# stepperboard1.net
KiCad netlist of a schematic drawn in EAGLE
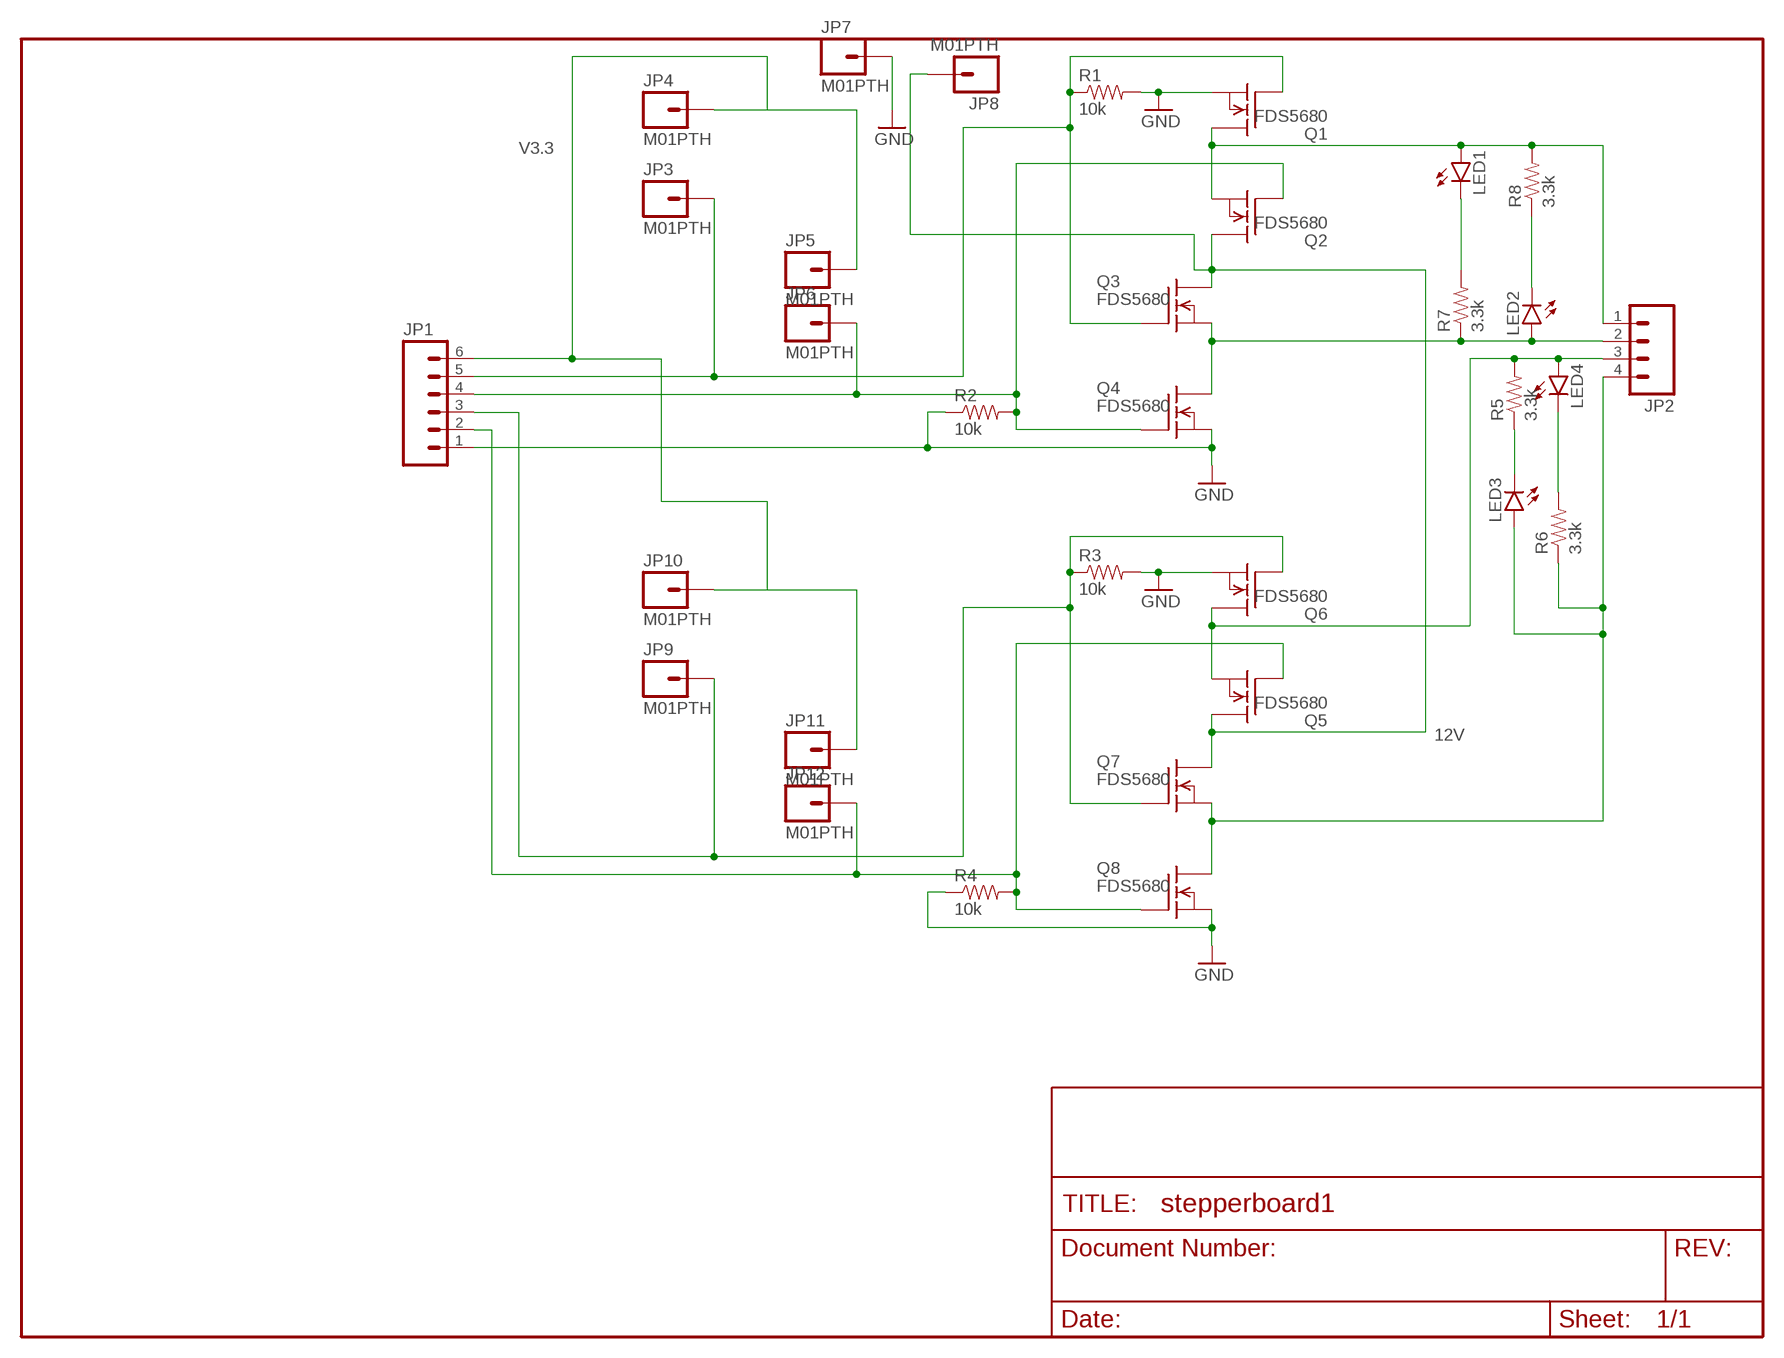
[diagram p0: schematic, sheet 1]

(export (version "E")
  (design (tool "Eeschema 10.0.6"))
  (components
    (comp (ref "JP1")
      (value "M06NO_SILK")
      (footprint "eagle-import:1X06_NO_SILK")
      (libsource (lib "eagle-import") (part "M06NO_SILK"))
    )
    (comp (ref "JP2")
      (value "M04LONGPADS")
      (footprint "eagle-import:1X04_LONGPADS")
      (libsource (lib "eagle-import") (part "M04LONGPADS"))
    )
    (comp (ref "JP3")
      (value "M01PTH")
      (footprint "eagle-import:1X01")
      (libsource (lib "eagle-import") (part "M01PTH"))
    )
    (comp (ref "JP4")
      (value "M01PTH")
      (footprint "eagle-import:1X01")
      (libsource (lib "eagle-import") (part "M01PTH"))
    )
    (comp (ref "JP5")
      (value "M01PTH")
      (footprint "eagle-import:1X01")
      (libsource (lib "eagle-import") (part "M01PTH"))
    )
    (comp (ref "JP6")
      (value "M01PTH")
      (footprint "eagle-import:1X01")
      (libsource (lib "eagle-import") (part "M01PTH"))
    )
    (comp (ref "JP7")
      (value "M01PTH")
      (footprint "eagle-import:1X01")
      (libsource (lib "eagle-import") (part "M01PTH"))
    )
    (comp (ref "JP8")
      (value "M01PTH")
      (footprint "eagle-import:1X01")
      (libsource (lib "eagle-import") (part "M01PTH"))
    )
    (comp (ref "JP9")
      (value "M01PTH")
      (footprint "eagle-import:1X01")
      (libsource (lib "eagle-import") (part "M01PTH"))
    )
    (comp (ref "JP10")
      (value "M01PTH")
      (footprint "eagle-import:1X01")
      (libsource (lib "eagle-import") (part "M01PTH"))
    )
    (comp (ref "JP11")
      (value "M01PTH")
      (footprint "eagle-import:1X01")
      (libsource (lib "eagle-import") (part "M01PTH"))
    )
    (comp (ref "JP12")
      (value "M01PTH")
      (footprint "eagle-import:1X01")
      (libsource (lib "eagle-import") (part "M01PTH"))
    )
    (comp (ref "LED1")
      (value "LED3MM")
      (footprint "eagle-import:LED3MM")
      (libsource (lib "eagle-import") (part "LED3MM"))
    )
    (comp (ref "LED2")
      (value "LED3MM")
      (footprint "eagle-import:LED3MM")
      (libsource (lib "eagle-import") (part "LED3MM"))
    )
    (comp (ref "LED3")
      (value "LED3MM")
      (footprint "eagle-import:LED3MM")
      (libsource (lib "eagle-import") (part "LED3MM"))
    )
    (comp (ref "LED4")
      (value "LED3MM")
      (footprint "eagle-import:LED3MM")
      (libsource (lib "eagle-import") (part "LED3MM"))
    )
    (comp (ref "Q1")
      (value "FDS5680")
      (footprint "eagle-import:SO-8")
      (libsource (lib "eagle-import") (part "FDS5680"))
    )
    (comp (ref "Q2")
      (value "FDS5680")
      (footprint "eagle-import:SO-8")
      (libsource (lib "eagle-import") (part "FDS5680"))
    )
    (comp (ref "Q3")
      (value "FDS5680")
      (footprint "eagle-import:SO-8")
      (libsource (lib "eagle-import") (part "FDS5680"))
    )
    (comp (ref "Q4")
      (value "FDS5680")
      (footprint "eagle-import:SO-8")
      (libsource (lib "eagle-import") (part "FDS5680"))
    )
    (comp (ref "Q5")
      (value "FDS5680")
      (footprint "eagle-import:SO-8")
      (libsource (lib "eagle-import") (part "FDS5680"))
    )
    (comp (ref "Q6")
      (value "FDS5680")
      (footprint "eagle-import:SO-8")
      (libsource (lib "eagle-import") (part "FDS5680"))
    )
    (comp (ref "Q7")
      (value "FDS5680")
      (footprint "eagle-import:SO-8")
      (libsource (lib "eagle-import") (part "FDS5680"))
    )
    (comp (ref "Q8")
      (value "FDS5680")
      (footprint "eagle-import:SO-8")
      (libsource (lib "eagle-import") (part "FDS5680"))
    )
    (comp (ref "R1")
      (value "10k")
      (footprint "eagle-import:0603-RES")
      (libsource (lib "eagle-import") (part "RESISTOR0603-RES"))
    )
    (comp (ref "R2")
      (value "10k")
      (footprint "eagle-import:0603-RES")
      (libsource (lib "eagle-import") (part "RESISTOR0603-RES"))
    )
    (comp (ref "R3")
      (value "10k")
      (footprint "eagle-import:0603-RES")
      (libsource (lib "eagle-import") (part "RESISTOR0603-RES"))
    )
    (comp (ref "R4")
      (value "10k")
      (footprint "eagle-import:0603-RES")
      (libsource (lib "eagle-import") (part "RESISTOR0603-RES"))
    )
    (comp (ref "R5")
      (value "3.3k")
      (footprint "eagle-import:0603-RES")
      (libsource (lib "eagle-import") (part "RESISTOR0603-RES"))
    )
    (comp (ref "R6")
      (value "3.3k")
      (footprint "eagle-import:0603-RES")
      (libsource (lib "eagle-import") (part "RESISTOR0603-RES"))
    )
    (comp (ref "R7")
      (value "3.3k")
      (footprint "eagle-import:0603-RES")
      (libsource (lib "eagle-import") (part "RESISTOR0603-RES"))
    )
    (comp (ref "R8")
      (value "3.3k")
      (footprint "eagle-import:0603-RES")
      (libsource (lib "eagle-import") (part "RESISTOR0603-RES"))
    )
  )
  (nets
    (net (code "1") (name "/12V") (class "Default")
      (node (ref "JP8") (pin "1") (pinfunction "1_1") (pintype "passive"))
      (node (ref "Q2") (pin "5") (pinfunction "D_5") (pintype "passive"))
      (node (ref "Q2") (pin "6") (pinfunction "D_6") (pintype "passive"))
      (node (ref "Q2") (pin "7") (pinfunction "D_7") (pintype "passive"))
      (node (ref "Q2") (pin "8") (pinfunction "D_8") (pintype "passive"))
      (node (ref "Q3") (pin "5") (pinfunction "D_5") (pintype "passive"))
      (node (ref "Q3") (pin "6") (pinfunction "D_6") (pintype "passive"))
      (node (ref "Q3") (pin "7") (pinfunction "D_7") (pintype "passive"))
      (node (ref "Q3") (pin "8") (pinfunction "D_8") (pintype "passive"))
      (node (ref "Q5") (pin "5") (pinfunction "D_5") (pintype "passive"))
      (node (ref "Q5") (pin "6") (pinfunction "D_6") (pintype "passive"))
      (node (ref "Q5") (pin "7") (pinfunction "D_7") (pintype "passive"))
      (node (ref "Q5") (pin "8") (pinfunction "D_8") (pintype "passive"))
      (node (ref "Q7") (pin "5") (pinfunction "D_5") (pintype "passive"))
      (node (ref "Q7") (pin "6") (pinfunction "D_6") (pintype "passive"))
      (node (ref "Q7") (pin "7") (pinfunction "D_7") (pintype "passive"))
      (node (ref "Q7") (pin "8") (pinfunction "D_8") (pintype "passive"))
    )
    (net (code "2") (name "/V3.3") (class "Default")
      (node (ref "JP1") (pin "6") (pinfunction "6_6") (pintype "passive"))
      (node (ref "JP10") (pin "1") (pinfunction "1_1") (pintype "passive"))
      (node (ref "JP11") (pin "1") (pinfunction "1_1") (pintype "passive"))
      (node (ref "JP4") (pin "1") (pinfunction "1_1") (pintype "passive"))
      (node (ref "JP5") (pin "1") (pinfunction "1_1") (pintype "passive"))
    )
    (net (code "3") (name "GND") (class "Default")
      (node (ref "JP1") (pin "1") (pinfunction "1_1") (pintype "passive"))
      (node (ref "JP7") (pin "1") (pinfunction "1_1") (pintype "passive"))
      (node (ref "Q1") (pin "1") (pinfunction "S_1") (pintype "passive"))
      (node (ref "Q1") (pin "2") (pinfunction "S_2") (pintype "passive"))
      (node (ref "Q1") (pin "3") (pinfunction "S_3") (pintype "passive"))
      (node (ref "Q4") (pin "1") (pinfunction "S_1") (pintype "passive"))
      (node (ref "Q4") (pin "2") (pinfunction "S_2") (pintype "passive"))
      (node (ref "Q4") (pin "3") (pinfunction "S_3") (pintype "passive"))
      (node (ref "Q6") (pin "1") (pinfunction "S_1") (pintype "passive"))
      (node (ref "Q6") (pin "2") (pinfunction "S_2") (pintype "passive"))
      (node (ref "Q6") (pin "3") (pinfunction "S_3") (pintype "passive"))
      (node (ref "Q8") (pin "1") (pinfunction "S_1") (pintype "passive"))
      (node (ref "Q8") (pin "2") (pinfunction "S_2") (pintype "passive"))
      (node (ref "Q8") (pin "3") (pinfunction "S_3") (pintype "passive"))
      (node (ref "R1") (pin "2") (pinfunction "2_2") (pintype "passive"))
      (node (ref "R2") (pin "1") (pinfunction "1_1") (pintype "passive"))
      (node (ref "R3") (pin "2") (pinfunction "2_2") (pintype "passive"))
      (node (ref "R4") (pin "1") (pinfunction "1_1") (pintype "passive"))
    )
    (net (code "4") (name "Net-(JP2-Pad1)") (class "Default")
      (node (ref "JP2") (pin "1") (pinfunction "1_1") (pintype "passive"))
      (node (ref "LED1") (pin "A") (pinfunction "A_A") (pintype "passive"))
      (node (ref "Q1") (pin "5") (pinfunction "D_5") (pintype "passive"))
      (node (ref "Q1") (pin "6") (pinfunction "D_6") (pintype "passive"))
      (node (ref "Q1") (pin "7") (pinfunction "D_7") (pintype "passive"))
      (node (ref "Q1") (pin "8") (pinfunction "D_8") (pintype "passive"))
      (node (ref "Q2") (pin "1") (pinfunction "S_1") (pintype "passive"))
      (node (ref "Q2") (pin "2") (pinfunction "S_2") (pintype "passive"))
      (node (ref "Q2") (pin "3") (pinfunction "S_3") (pintype "passive"))
      (node (ref "R8") (pin "2") (pinfunction "2_2") (pintype "passive"))
    )
    (net (code "5") (name "Net-(JP2-Pad2)") (class "Default")
      (node (ref "JP2") (pin "2") (pinfunction "2_2") (pintype "passive"))
      (node (ref "LED2") (pin "A") (pinfunction "A_A") (pintype "passive"))
      (node (ref "Q3") (pin "1") (pinfunction "S_1") (pintype "passive"))
      (node (ref "Q3") (pin "2") (pinfunction "S_2") (pintype "passive"))
      (node (ref "Q3") (pin "3") (pinfunction "S_3") (pintype "passive"))
      (node (ref "Q4") (pin "5") (pinfunction "D_5") (pintype "passive"))
      (node (ref "Q4") (pin "6") (pinfunction "D_6") (pintype "passive"))
      (node (ref "Q4") (pin "7") (pinfunction "D_7") (pintype "passive"))
      (node (ref "Q4") (pin "8") (pinfunction "D_8") (pintype "passive"))
      (node (ref "R7") (pin "1") (pinfunction "1_1") (pintype "passive"))
    )
    (net (code "6") (name "Net-(JP2-Pad3)") (class "Default")
      (node (ref "JP2") (pin "3") (pinfunction "3_3") (pintype "passive"))
      (node (ref "LED4") (pin "A") (pinfunction "A_A") (pintype "passive"))
      (node (ref "Q5") (pin "1") (pinfunction "S_1") (pintype "passive"))
      (node (ref "Q5") (pin "2") (pinfunction "S_2") (pintype "passive"))
      (node (ref "Q5") (pin "3") (pinfunction "S_3") (pintype "passive"))
      (node (ref "Q6") (pin "5") (pinfunction "D_5") (pintype "passive"))
      (node (ref "Q6") (pin "6") (pinfunction "D_6") (pintype "passive"))
      (node (ref "Q6") (pin "7") (pinfunction "D_7") (pintype "passive"))
      (node (ref "Q6") (pin "8") (pinfunction "D_8") (pintype "passive"))
      (node (ref "R5") (pin "2") (pinfunction "2_2") (pintype "passive"))
    )
    (net (code "7") (name "Net-(JP2-Pad4)") (class "Default")
      (node (ref "JP2") (pin "4") (pinfunction "4_4") (pintype "passive"))
      (node (ref "LED3") (pin "A") (pinfunction "A_A") (pintype "passive"))
      (node (ref "Q7") (pin "1") (pinfunction "S_1") (pintype "passive"))
      (node (ref "Q7") (pin "2") (pinfunction "S_2") (pintype "passive"))
      (node (ref "Q7") (pin "3") (pinfunction "S_3") (pintype "passive"))
      (node (ref "Q8") (pin "5") (pinfunction "D_5") (pintype "passive"))
      (node (ref "Q8") (pin "6") (pinfunction "D_6") (pintype "passive"))
      (node (ref "Q8") (pin "7") (pinfunction "D_7") (pintype "passive"))
      (node (ref "Q8") (pin "8") (pinfunction "D_8") (pintype "passive"))
      (node (ref "R6") (pin "1") (pinfunction "1_1") (pintype "passive"))
    )
    (net (code "8") (name "Net-(LED1-C)") (class "Default")
      (node (ref "LED1") (pin "K") (pinfunction "C_K") (pintype "passive"))
      (node (ref "R7") (pin "2") (pinfunction "2_2") (pintype "passive"))
    )
    (net (code "9") (name "Net-(LED2-C)") (class "Default")
      (node (ref "LED2") (pin "K") (pinfunction "C_K") (pintype "passive"))
      (node (ref "R8") (pin "1") (pinfunction "1_1") (pintype "passive"))
    )
    (net (code "10") (name "Net-(LED3-C)") (class "Default")
      (node (ref "LED3") (pin "K") (pinfunction "C_K") (pintype "passive"))
      (node (ref "R5") (pin "1") (pinfunction "1_1") (pintype "passive"))
    )
    (net (code "11") (name "Net-(LED4-C)") (class "Default")
      (node (ref "LED4") (pin "K") (pinfunction "C_K") (pintype "passive"))
      (node (ref "R6") (pin "2") (pinfunction "2_2") (pintype "passive"))
    )
    (net (code "12") (name "Net-(Q1-G)") (class "Default")
      (node (ref "JP1") (pin "5") (pinfunction "5_5") (pintype "passive"))
      (node (ref "JP3") (pin "1") (pinfunction "1_1") (pintype "passive"))
      (node (ref "Q1") (pin "4") (pinfunction "G_4") (pintype "passive"))
      (node (ref "Q3") (pin "4") (pinfunction "G_4") (pintype "passive"))
      (node (ref "R1") (pin "1") (pinfunction "1_1") (pintype "passive"))
    )
    (net (code "13") (name "Net-(Q2-G)") (class "Default")
      (node (ref "JP1") (pin "4") (pinfunction "4_4") (pintype "passive"))
      (node (ref "JP6") (pin "1") (pinfunction "1_1") (pintype "passive"))
      (node (ref "Q2") (pin "4") (pinfunction "G_4") (pintype "passive"))
      (node (ref "Q4") (pin "4") (pinfunction "G_4") (pintype "passive"))
      (node (ref "R2") (pin "2") (pinfunction "2_2") (pintype "passive"))
    )
    (net (code "14") (name "Net-(Q5-G)") (class "Default")
      (node (ref "JP1") (pin "2") (pinfunction "2_2") (pintype "passive"))
      (node (ref "JP12") (pin "1") (pinfunction "1_1") (pintype "passive"))
      (node (ref "Q5") (pin "4") (pinfunction "G_4") (pintype "passive"))
      (node (ref "Q8") (pin "4") (pinfunction "G_4") (pintype "passive"))
      (node (ref "R4") (pin "2") (pinfunction "2_2") (pintype "passive"))
    )
    (net (code "15") (name "Net-(Q6-G)") (class "Default")
      (node (ref "JP1") (pin "3") (pinfunction "3_3") (pintype "passive"))
      (node (ref "JP9") (pin "1") (pinfunction "1_1") (pintype "passive"))
      (node (ref "Q6") (pin "4") (pinfunction "G_4") (pintype "passive"))
      (node (ref "Q7") (pin "4") (pinfunction "G_4") (pintype "passive"))
      (node (ref "R3") (pin "1") (pinfunction "1_1") (pintype "passive"))
    )
  )
)
